# Adafruit_ItsyBitsy_M4.net
KiCad netlist of a schematic drawn in EAGLE
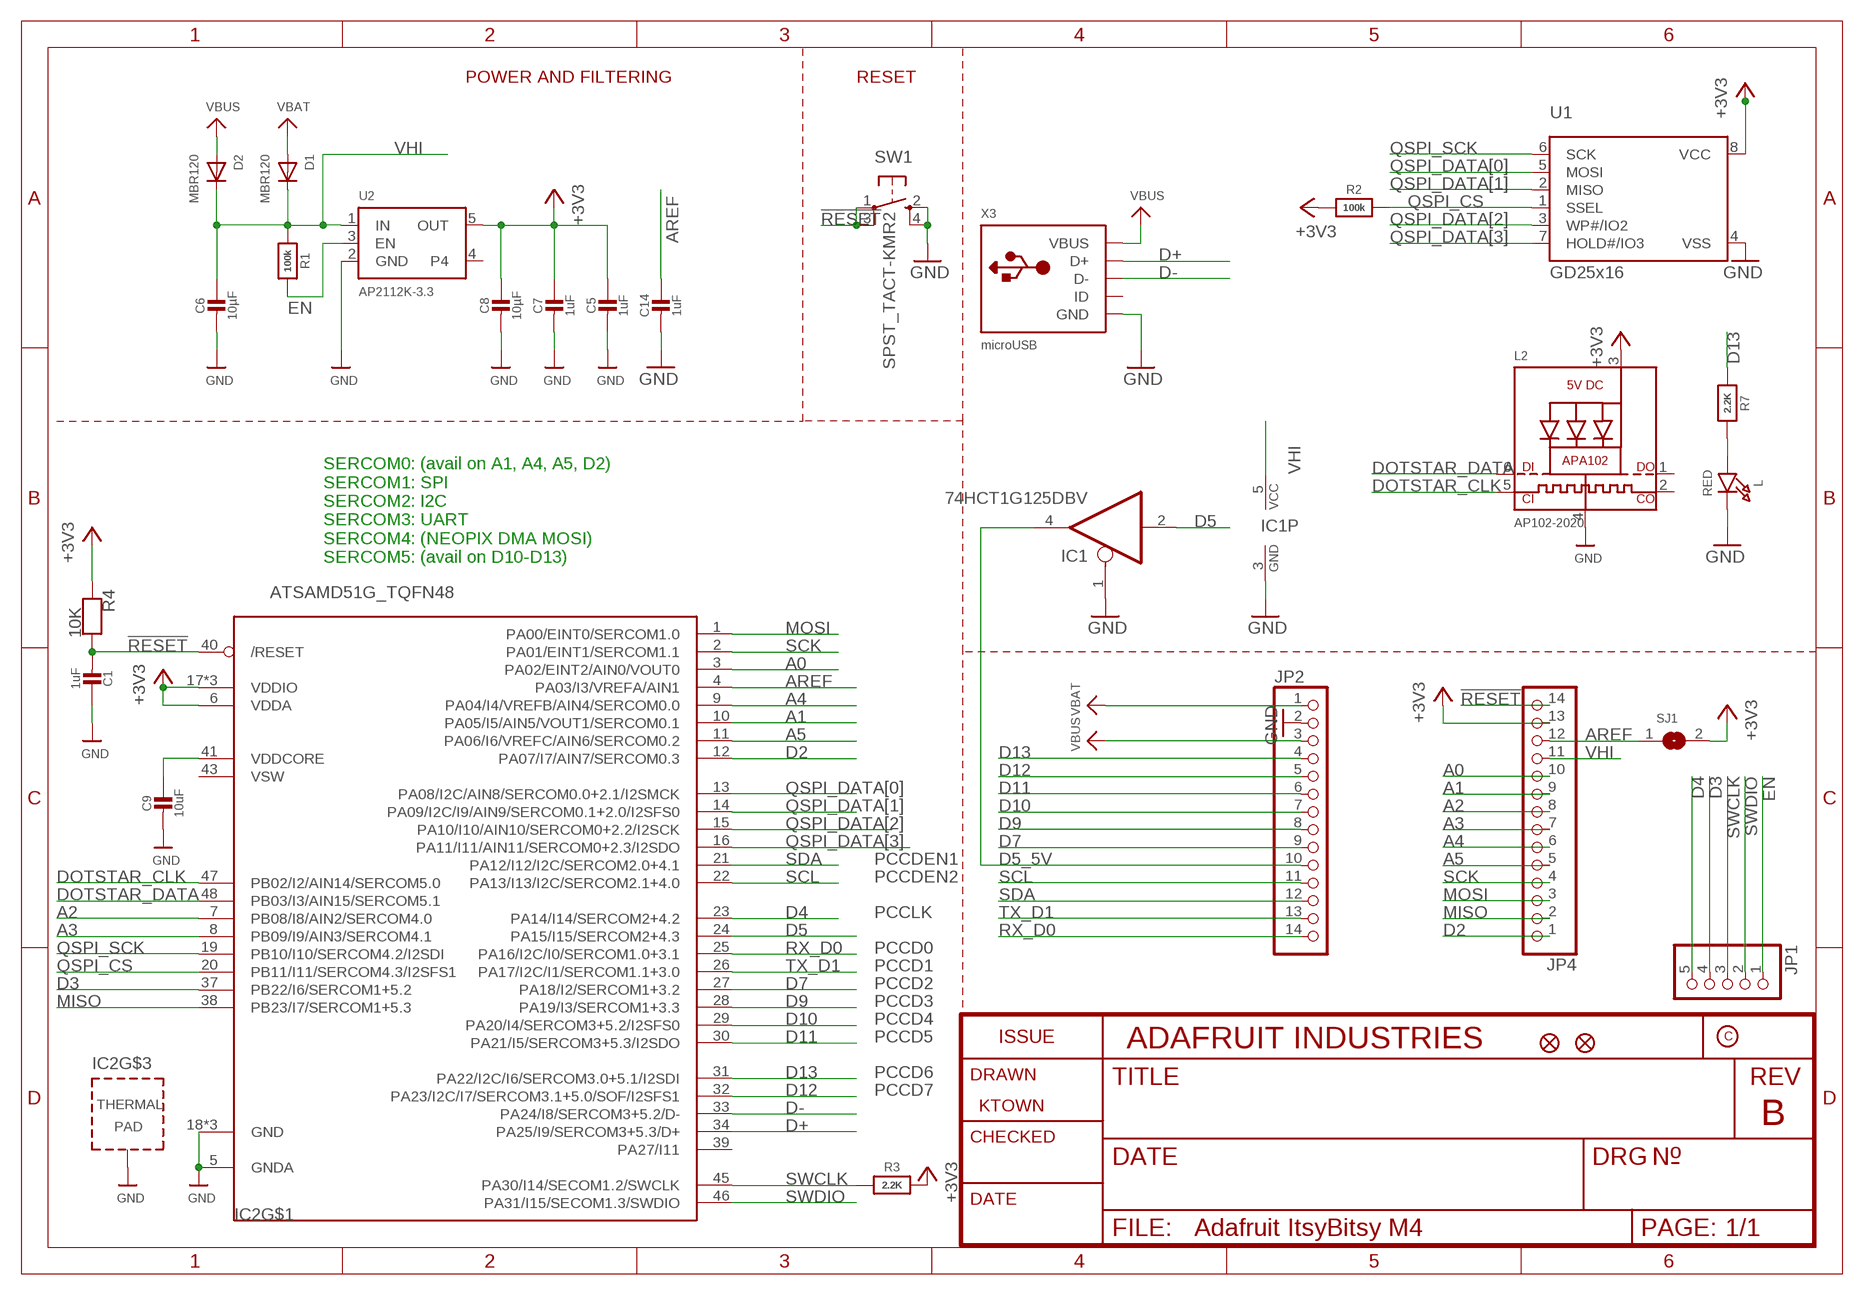
[diagram p0: schematic, sheet 1]

(export (version "E")
  (design (tool "Eeschema 10.0.6"))
  (components
    (comp (ref "C1")
      (value "1uF")
      (footprint "eagle-import:_0603MP")
      (libsource (lib "eagle-import") (part "CAP_CERAMIC_0603MP"))
    )
    (comp (ref "C5")
      (value "1uF")
      (footprint "eagle-import:0603-NO")
      (libsource (lib "eagle-import") (part "CAP_CERAMIC0603_NO"))
    )
    (comp (ref "C6")
      (value "10µF")
      (footprint "eagle-import:0805-NO")
      (libsource (lib "eagle-import") (part "CAP_CERAMIC0805-NOOUTLINE"))
    )
    (comp (ref "C7")
      (value "1uF")
      (footprint "eagle-import:0603-NO")
      (libsource (lib "eagle-import") (part "CAP_CERAMIC0603_NO"))
    )
    (comp (ref "C8")
      (value "10µF")
      (footprint "eagle-import:0805-NO")
      (libsource (lib "eagle-import") (part "CAP_CERAMIC0805-NOOUTLINE"))
    )
    (comp (ref "C9")
      (value "10uF")
      (footprint "eagle-import:_0805MP")
      (libsource (lib "eagle-import") (part "CAP_CERAMIC_0805MP"))
    )
    (comp (ref "C14")
      (value "1uF")
      (footprint "eagle-import:0603-NO")
      (libsource (lib "eagle-import") (part "CAP_CERAMIC0603_NO"))
    )
    (comp (ref "D1")
      (value "MBR120")
      (footprint "eagle-import:SOD-123FL")
      (libsource (lib "eagle-import") (part "DIODE_SOD-123FL"))
    )
    (comp (ref "D2")
      (value "MBR120")
      (footprint "eagle-import:SOD-123FL")
      (libsource (lib "eagle-import") (part "DIODE_SOD-123FL"))
    )
    (comp (ref "IC1")
      (value "74HCT1G125DBV")
      (footprint "eagle-import:SOT23-5")
      (libsource (lib "eagle-import") (part "741G125DBVAHC"))
    )
    (comp (ref "IC2")
      (value "ATSAMD51G_TQFN48")
      (footprint "eagle-import:TQFN48_7MM")
      (libsource (lib "eagle-import") (part "ATSAMD51G_TQFN48"))
    )
    (comp (ref "JP1")
      (value "HEADER-1X570MIL")
      (footprint "eagle-import:1X05_ROUND_70")
      (libsource (lib "eagle-import") (part "HEADER-1X570MIL"))
    )
    (comp (ref "JP2")
      (value "HEADER-1X14")
      (footprint "eagle-import:1X14_ROUND70")
      (libsource (lib "eagle-import") (part "HEADER-1X14"))
    )
    (comp (ref "JP4")
      (value "HEADER-1X14")
      (footprint "eagle-import:1X14_ROUND70")
      (libsource (lib "eagle-import") (part "HEADER-1X14"))
    )
    (comp (ref "L")
      (value "RED")
      (footprint "eagle-import:CHIPLED_0603_NOOUTLINE")
      (libsource (lib "eagle-import") (part "LED0603_NOOUTLINE"))
    )
    (comp (ref "L2")
      (value "AP102-2020")
      (footprint "eagle-import:APA102_2020")
      (libsource (lib "eagle-import") (part "APA1022020"))
    )
    (comp (ref "R1")
      (value "100k")
      (footprint "eagle-import:0603-NO")
      (libsource (lib "eagle-import") (part "RESISTOR_0603_NOOUT"))
    )
    (comp (ref "R2")
      (value "100k")
      (footprint "eagle-import:0603-NO")
      (libsource (lib "eagle-import") (part "RESISTOR_0603_NOOUT"))
    )
    (comp (ref "R3")
      (value "2.2K")
      (footprint "eagle-import:_0603MP")
      (libsource (lib "eagle-import") (part "RESISTOR_0603MP"))
    )
    (comp (ref "R4")
      (value "10K")
      (footprint "eagle-import:_0603MP")
      (libsource (lib "eagle-import") (part "RESISTOR_0603MP"))
    )
    (comp (ref "R7")
      (value "2.2K")
      (footprint "eagle-import:0603-NO")
      (libsource (lib "eagle-import") (part "RESISTOR_0603_NOOUT"))
    )
    (comp (ref "SJ1")
      (value "SOLDERJUMPERCLOSED")
      (footprint "eagle-import:SOLDERJUMPER_CLOSEDWIRE")
      (libsource (lib "eagle-import") (part "SOLDERJUMPERCLOSED"))
    )
    (comp (ref "SW1")
      (value "SPST_TACT-KMR2")
      (footprint "eagle-import:KMR2")
      (libsource (lib "eagle-import") (part "SPST_TACT-KMR2"))
    )
    (comp (ref "U$34")
      (value "FIDUCIAL_1MM")
      (footprint "eagle-import:FIDUCIAL_1MM")
      (libsource (lib "eagle-import") (part "FIDUCIAL_1MM"))
    )
    (comp (ref "U$35")
      (value "FIDUCIAL_1MM")
      (footprint "eagle-import:FIDUCIAL_1MM")
      (libsource (lib "eagle-import") (part "FIDUCIAL_1MM"))
    )
    (comp (ref "U1")
      (value "GD25x16")
      (footprint "eagle-import:USON8")
      (libsource (lib "eagle-import") (part "SPIFLASH_8PINUX"))
    )
    (comp (ref "U2")
      (value "AP2112K-3.3")
      (footprint "eagle-import:SOT23-5")
      (libsource (lib "eagle-import") (part "VREG_SOT23-5"))
    )
    (comp (ref "X3")
      (value "microUSB")
      (footprint "eagle-import:4UCONN_20329_V2")
      (libsource (lib "eagle-import") (part "USB_MICRO_20329_V2"))
    )
  )
  (nets
    (net (code "1") (name "+3V3") (class "Default")
      (node (ref "C5") (pin "1") (pinfunction "1_1") (pintype "passive"))
      (node (ref "C7") (pin "1") (pinfunction "1_1") (pintype "passive"))
      (node (ref "C8") (pin "1") (pinfunction "1_1") (pintype "passive"))
      (node (ref "IC2") (pin "17") (pinfunction "VDDIO_17") (pintype "power_in"))
      (node (ref "IC2") (pin "36") (pinfunction "VDDIO_36") (pintype "power_in"))
      (node (ref "IC2") (pin "44") (pinfunction "VDDIO_44") (pintype "power_in"))
      (node (ref "IC2") (pin "6") (pinfunction "VDDA_6") (pintype "power_in"))
      (node (ref "JP4") (pin "13") (pinfunction "13_13") (pintype "passive"))
      (node (ref "L2") (pin "3") (pinfunction "VDD_3") (pintype "power_in"))
      (node (ref "R2") (pin "1") (pinfunction "1_1") (pintype "passive"))
      (node (ref "R3") (pin "2") (pinfunction "2_2") (pintype "passive"))
      (node (ref "R4") (pin "1") (pinfunction "1_1") (pintype "passive"))
      (node (ref "SJ1") (pin "2") (pinfunction "2_2") (pintype "passive"))
      (node (ref "U1") (pin "8") (pinfunction "VCC_8") (pintype "bidirectional"))
      (node (ref "U2") (pin "5") (pinfunction "OUT_5") (pintype "power_in"))
    )
    (net (code "2") (name "/A0") (class "Default")
      (node (ref "IC2") (pin "3") (pinfunction "PA02/EINT2/AIN0/VOUT0_3") (pintype "bidirectional"))
      (node (ref "JP4") (pin "10") (pinfunction "10_10") (pintype "passive"))
    )
    (net (code "3") (name "/A1") (class "Default")
      (node (ref "IC2") (pin "10") (pinfunction "PA05/I5/AIN5/VOUT1/SERCOM0.1_10") (pintype "bidirectional"))
      (node (ref "JP4") (pin "9") (pinfunction "9_9") (pintype "passive"))
    )
    (net (code "4") (name "/A2") (class "Default")
      (node (ref "IC2") (pin "7") (pinfunction "PB08/I8/AIN2/SERCOM4.0_7") (pintype "bidirectional"))
      (node (ref "JP4") (pin "8") (pinfunction "8_8") (pintype "passive"))
    )
    (net (code "5") (name "/A3") (class "Default")
      (node (ref "IC2") (pin "8") (pinfunction "PB09/I9/AIN3/SERCOM4.1_8") (pintype "bidirectional"))
      (node (ref "JP4") (pin "7") (pinfunction "7_7") (pintype "passive"))
    )
    (net (code "6") (name "/A4") (class "Default")
      (node (ref "IC2") (pin "9") (pinfunction "PA04/I4/VREFB/AIN4/SERCOM0.0_9") (pintype "bidirectional"))
      (node (ref "JP4") (pin "6") (pinfunction "6_6") (pintype "passive"))
    )
    (net (code "7") (name "/A5") (class "Default")
      (node (ref "IC2") (pin "11") (pinfunction "PA06/I6/VREFC/AIN6/SERCOM0.2_11") (pintype "bidirectional"))
      (node (ref "JP4") (pin "5") (pinfunction "5_5") (pintype "passive"))
    )
    (net (code "8") (name "/AREF") (class "Default")
      (node (ref "C14") (pin "1") (pinfunction "1_1") (pintype "passive"))
      (node (ref "IC2") (pin "4") (pinfunction "PA03/I3/VREFA/AIN1_4") (pintype "bidirectional"))
      (node (ref "JP4") (pin "12") (pinfunction "12_12") (pintype "passive"))
      (node (ref "SJ1") (pin "1") (pinfunction "1_1") (pintype "passive"))
    )
    (net (code "9") (name "/D+") (class "Default")
      (node (ref "IC2") (pin "34") (pinfunction "PA25/I9/SERCOM3+5.3/D+_34") (pintype "bidirectional"))
      (node (ref "X3") (pin "D+") (pinfunction "D+_D+") (pintype "bidirectional"))
    )
    (net (code "10") (name "/D-") (class "Default")
      (node (ref "IC2") (pin "33") (pinfunction "PA24/I8/SERCOM3+5.2/D-_33") (pintype "bidirectional"))
      (node (ref "X3") (pin "D-") (pinfunction "D-_D-") (pintype "bidirectional"))
    )
    (net (code "11") (name "/D2") (class "Default")
      (node (ref "IC2") (pin "12") (pinfunction "PA07/I7/AIN7/SERCOM0.3_12") (pintype "bidirectional"))
      (node (ref "JP4") (pin "1") (pinfunction "1_1") (pintype "passive"))
    )
    (net (code "12") (name "/D3") (class "Default")
      (node (ref "IC2") (pin "37") (pinfunction "PB22/I6/SERCOM1+5.2_37") (pintype "bidirectional"))
      (node (ref "JP1") (pin "4") (pinfunction "4_4") (pintype "passive"))
    )
    (net (code "13") (name "/D4") (class "Default")
      (node (ref "IC2") (pin "23") (pinfunction "PA14/I14/SERCOM2+4.2_23") (pintype "bidirectional"))
      (node (ref "JP1") (pin "5") (pinfunction "5_5") (pintype "passive"))
    )
    (net (code "14") (name "/D5") (class "Default")
      (node (ref "IC1") (pin "2") (pinfunction "I_2") (pintype "input"))
      (node (ref "IC2") (pin "24") (pinfunction "PA15/I15/SERCOM2+4.3_24") (pintype "bidirectional"))
    )
    (net (code "15") (name "/D5_5V") (class "Default")
      (node (ref "IC1") (pin "4") (pinfunction "O_4") (pintype "tri_state"))
      (node (ref "JP2") (pin "10") (pinfunction "10_10") (pintype "passive"))
    )
    (net (code "16") (name "/D7") (class "Default")
      (node (ref "IC2") (pin "27") (pinfunction "PA18/I2/SERCOM1+3.2_27") (pintype "bidirectional"))
      (node (ref "JP2") (pin "9") (pinfunction "9_9") (pintype "passive"))
    )
    (net (code "17") (name "/D9") (class "Default")
      (node (ref "IC2") (pin "28") (pinfunction "PA19/I3/SERCOM1+3.3_28") (pintype "bidirectional"))
      (node (ref "JP2") (pin "8") (pinfunction "8_8") (pintype "passive"))
    )
    (net (code "18") (name "/D10") (class "Default")
      (node (ref "IC2") (pin "29") (pinfunction "PA20/I4/SERCOM3+5.2/I2SFS0_29") (pintype "bidirectional"))
      (node (ref "JP2") (pin "7") (pinfunction "7_7") (pintype "passive"))
    )
    (net (code "19") (name "/D11") (class "Default")
      (node (ref "IC2") (pin "30") (pinfunction "PA21/I5/SERCOM3+5.3/I2SDO_30") (pintype "bidirectional"))
      (node (ref "JP2") (pin "6") (pinfunction "6_6") (pintype "passive"))
    )
    (net (code "20") (name "/D12") (class "Default")
      (node (ref "IC2") (pin "32") (pinfunction "PA23/I2C/I7/SERCOM3.1+5.0/SOF/I2SFS1_32") (pintype "bidirectional"))
      (node (ref "JP2") (pin "5") (pinfunction "5_5") (pintype "passive"))
    )
    (net (code "21") (name "/D13") (class "Default")
      (node (ref "IC2") (pin "31") (pinfunction "PA22/I2C/I6/SERCOM3.0+5.1/I2SDI_31") (pintype "bidirectional"))
      (node (ref "JP2") (pin "4") (pinfunction "4_4") (pintype "passive"))
      (node (ref "R7") (pin "1") (pinfunction "1_1") (pintype "passive"))
    )
    (net (code "22") (name "/DOTSTAR_CLK") (class "Default")
      (node (ref "IC2") (pin "47") (pinfunction "PB02/I2/AIN14/SERCOM5.0_47") (pintype "bidirectional"))
      (node (ref "L2") (pin "5") (pinfunction "CKI_5") (pintype "input"))
    )
    (net (code "23") (name "/DOTSTAR_DATA") (class "Default")
      (node (ref "IC2") (pin "48") (pinfunction "PB03/I3/AIN15/SERCOM5.1_48") (pintype "bidirectional"))
      (node (ref "L2") (pin "6") (pinfunction "DI_6") (pintype "input"))
    )
    (net (code "24") (name "/EN") (class "Default")
      (node (ref "JP1") (pin "1") (pinfunction "1_1") (pintype "passive"))
      (node (ref "R1") (pin "2") (pinfunction "2_2") (pintype "passive"))
      (node (ref "U2") (pin "3") (pinfunction "EN_3") (pintype "input"))
    )
    (net (code "25") (name "/MISO") (class "Default")
      (node (ref "IC2") (pin "38") (pinfunction "PB23/I7/SERCOM1+5.3_38") (pintype "bidirectional"))
      (node (ref "JP4") (pin "2") (pinfunction "2_2") (pintype "passive"))
    )
    (net (code "26") (name "/MOSI") (class "Default")
      (node (ref "IC2") (pin "1") (pinfunction "PA00/EINT0/SERCOM1.0_1") (pintype "bidirectional"))
      (node (ref "JP4") (pin "3") (pinfunction "3_3") (pintype "passive"))
    )
    (net (code "27") (name "/QSPI_CS") (class "Default")
      (node (ref "IC2") (pin "20") (pinfunction "PB11/I11/SERCOM4.3/I2SFS1_20") (pintype "bidirectional"))
      (node (ref "R2") (pin "2") (pinfunction "2_2") (pintype "passive"))
      (node (ref "U1") (pin "1") (pinfunction "SSEL_1") (pintype "bidirectional"))
    )
    (net (code "28") (name "/QSPI_DATA[0]") (class "Default")
      (node (ref "IC2") (pin "13") (pinfunction "PA08/I2C/AIN8/SERCOM0.0+2.1/I2SMCK_13") (pintype "bidirectional"))
      (node (ref "U1") (pin "5") (pinfunction "MOSI_5") (pintype "bidirectional"))
    )
    (net (code "29") (name "/QSPI_DATA[1]") (class "Default")
      (node (ref "IC2") (pin "14") (pinfunction "PA09/I2C/I9/AIN9/SERCOM0.1+2.0/I2SFS0_14") (pintype "bidirectional"))
      (node (ref "U1") (pin "2") (pinfunction "MISO_2") (pintype "bidirectional"))
    )
    (net (code "30") (name "/QSPI_DATA[2]") (class "Default")
      (node (ref "IC2") (pin "15") (pinfunction "PA10/I10/AIN10/SERCOM0+2.2/I2SCK_15") (pintype "bidirectional"))
      (node (ref "U1") (pin "3") (pinfunction "WP#/IO2_3") (pintype "bidirectional"))
    )
    (net (code "31") (name "/QSPI_DATA[3]") (class "Default")
      (node (ref "IC2") (pin "16") (pinfunction "PA11/I11/AIN11/SERCOM0+2.3/I2SDO_16") (pintype "bidirectional"))
      (node (ref "U1") (pin "7") (pinfunction "HOLD#/IO3_7") (pintype "bidirectional"))
    )
    (net (code "32") (name "/QSPI_SCK") (class "Default")
      (node (ref "IC2") (pin "19") (pinfunction "PB10/I10/SERCOM4.2/I2SDI_19") (pintype "bidirectional"))
      (node (ref "U1") (pin "6") (pinfunction "SCK_6") (pintype "bidirectional"))
    )
    (net (code "33") (name "/RX_D0") (class "Default")
      (node (ref "IC2") (pin "25") (pinfunction "PA16/I2C/I0/SERCOM1.0+3.1_25") (pintype "bidirectional"))
      (node (ref "JP2") (pin "14") (pinfunction "14_14") (pintype "passive"))
    )
    (net (code "34") (name "/SCK") (class "Default")
      (node (ref "IC2") (pin "2") (pinfunction "PA01/EINT1/SERCOM1.1_2") (pintype "bidirectional"))
      (node (ref "JP4") (pin "4") (pinfunction "4_4") (pintype "passive"))
    )
    (net (code "35") (name "/SCL") (class "Default")
      (node (ref "IC2") (pin "22") (pinfunction "PA13/I13/I2C/SERCOM2.1+4.0_22") (pintype "bidirectional"))
      (node (ref "JP2") (pin "11") (pinfunction "11_11") (pintype "passive"))
    )
    (net (code "36") (name "/SDA") (class "Default")
      (node (ref "IC2") (pin "21") (pinfunction "PA12/I12/I2C/SERCOM2.0+4.1_21") (pintype "bidirectional"))
      (node (ref "JP2") (pin "12") (pinfunction "12_12") (pintype "passive"))
    )
    (net (code "37") (name "/SWCLK") (class "Default")
      (node (ref "IC2") (pin "45") (pinfunction "PA30/I14/SECOM1.2/SWCLK_45") (pintype "bidirectional"))
      (node (ref "JP1") (pin "3") (pinfunction "3_3") (pintype "passive"))
      (node (ref "R3") (pin "1") (pinfunction "1_1") (pintype "passive"))
    )
    (net (code "38") (name "/SWDIO") (class "Default")
      (node (ref "IC2") (pin "46") (pinfunction "PA31/I15/SECOM1.3/SWDIO_46") (pintype "bidirectional"))
      (node (ref "JP1") (pin "2") (pinfunction "2_2") (pintype "passive"))
    )
    (net (code "39") (name "/TX_D1") (class "Default")
      (node (ref "IC2") (pin "26") (pinfunction "PA17/I2C/I1/SERCOM1.1+3.0_26") (pintype "bidirectional"))
      (node (ref "JP2") (pin "13") (pinfunction "13_13") (pintype "passive"))
    )
    (net (code "40") (name "/VHI") (class "Default")
      (node (ref "C6") (pin "1") (pinfunction "1_1") (pintype "passive"))
      (node (ref "D1") (pin "C") (pinfunction "C_C") (pintype "passive"))
      (node (ref "D2") (pin "C") (pinfunction "C_C") (pintype "passive"))
      (node (ref "IC1") (pin "5") (pinfunction "VCC_5") (pintype "power_in"))
      (node (ref "JP4") (pin "11") (pinfunction "11_11") (pintype "passive"))
      (node (ref "R1") (pin "1") (pinfunction "1_1") (pintype "passive"))
      (node (ref "U2") (pin "1") (pinfunction "IN_1") (pintype "power_in"))
    )
    (net (code "41") (name "/VSW") (class "Default")
      (node (ref "IC2") (pin "43") (pinfunction "VSW_43") (pintype "power_in"))
    )
    (net (code "42") (name "/~{RESET}") (class "Default")
      (node (ref "C1") (pin "2") (pinfunction "2_2") (pintype "passive"))
      (node (ref "IC2") (pin "40") (pinfunction "/RESET_40") (pintype "bidirectional"))
      (node (ref "JP4") (pin "14") (pinfunction "14_14") (pintype "passive"))
      (node (ref "R4") (pin "2") (pinfunction "2_2") (pintype "passive"))
      (node (ref "SW1") (pin "1") (pinfunction "P_1") (pintype "passive"))
      (node (ref "SW1") (pin "3") (pinfunction "P1_3") (pintype "passive"))
    )
    (net (code "43") (name "GND") (class "Default")
      (node (ref "C1") (pin "1") (pinfunction "1_1") (pintype "passive"))
      (node (ref "C14") (pin "2") (pinfunction "2_2") (pintype "passive"))
      (node (ref "C5") (pin "2") (pinfunction "2_2") (pintype "passive"))
      (node (ref "C6") (pin "2") (pinfunction "2_2") (pintype "passive"))
      (node (ref "C7") (pin "2") (pinfunction "2_2") (pintype "passive"))
      (node (ref "C8") (pin "2") (pinfunction "2_2") (pintype "passive"))
      (node (ref "C9") (pin "2") (pinfunction "2_2") (pintype "passive"))
      (node (ref "IC1") (pin "1") (pinfunction "OE_1") (pintype "input"))
      (node (ref "IC1") (pin "3") (pinfunction "GND_3") (pintype "power_in"))
      (node (ref "IC2") (pin "18") (pinfunction "GND_18") (pintype "power_in"))
      (node (ref "IC2") (pin "35") (pinfunction "GND_35") (pintype "power_in"))
      (node (ref "IC2") (pin "42") (pinfunction "GND_42") (pintype "power_in"))
      (node (ref "IC2") (pin "5") (pinfunction "GNDA_5") (pintype "power_in"))
      (node (ref "IC2") (pin "THERMAL") (pinfunction "TP_THERMAL") (pintype "power_in"))
      (node (ref "JP2") (pin "2") (pinfunction "2_2") (pintype "passive"))
      (node (ref "L") (pin "C") (pinfunction "C_C") (pintype "passive"))
      (node (ref "L2") (pin "4") (pinfunction "GND_4") (pintype "power_in"))
      (node (ref "SW1") (pin "2") (pinfunction "S_2") (pintype "passive"))
      (node (ref "SW1") (pin "4") (pinfunction "S1_4") (pintype "passive"))
      (node (ref "U1") (pin "4") (pinfunction "VSS_4") (pintype "bidirectional"))
      (node (ref "U2") (pin "2") (pinfunction "GND_2") (pintype "power_in"))
      (node (ref "X3") (pin "BASE@1") (pinfunction "GND_BASE@1") (pintype "power_in"))
      (node (ref "X3") (pin "BASE@2") (pinfunction "GND_BASE@2") (pintype "power_in"))
      (node (ref "X3") (pin "GND") (pinfunction "GND_GND") (pintype "power_in"))
      (node (ref "X3") (pin "SPRT@1") (pinfunction "GND_SPRT@1") (pintype "power_in"))
      (node (ref "X3") (pin "SPRT@2") (pinfunction "GND_SPRT@2") (pintype "power_in"))
      (node (ref "X3") (pin "SPRT@3") (pinfunction "GND_SPRT@3") (pintype "power_in"))
      (node (ref "X3") (pin "SPRT@4") (pinfunction "GND_SPRT@4") (pintype "power_in"))
    )
    (net (code "44") (name "Net-(IC2A-VDDCORE)") (class "Default")
      (node (ref "C9") (pin "1") (pinfunction "1_1") (pintype "passive"))
      (node (ref "IC2") (pin "41") (pinfunction "VDDCORE_41") (pintype "power_in"))
    )
    (net (code "45") (name "Net-(L-PadA)") (class "Default")
      (node (ref "L") (pin "A") (pinfunction "A_A") (pintype "passive"))
      (node (ref "R7") (pin "2") (pinfunction "2_2") (pintype "passive"))
    )
    (net (code "46") (name "VBAT") (class "Default")
      (node (ref "D1") (pin "A") (pinfunction "A_A") (pintype "passive"))
      (node (ref "JP2") (pin "1") (pinfunction "1_1") (pintype "passive"))
    )
    (net (code "47") (name "VBUS") (class "Default")
      (node (ref "D2") (pin "A") (pinfunction "A_A") (pintype "passive"))
      (node (ref "JP2") (pin "3") (pinfunction "3_3") (pintype "passive"))
      (node (ref "X3") (pin "VBUS") (pinfunction "VBUS_VBUS") (pintype "power_in"))
    )
    (net (code "48") (name "unconnected-(IC2A-PA27{slash}I11-Pad39)") (class "Default")
      (node (ref "IC2") (pin "39") (pinfunction "PA27/I11_39") (pintype "bidirectional"))
    )
    (net (code "49") (name "unconnected-(L2-CKO-Pad2)") (class "Default")
      (node (ref "L2") (pin "2") (pinfunction "CKO_2") (pintype "output"))
    )
    (net (code "50") (name "unconnected-(L2-DO-Pad1)") (class "Default")
      (node (ref "L2") (pin "1") (pinfunction "DO_1") (pintype "output"))
    )
    (net (code "51") (name "unconnected-(U2-P4-Pad4)") (class "Default")
      (node (ref "U2") (pin "4") (pinfunction "P4_4") (pintype "bidirectional"))
    )
    (net (code "52") (name "unconnected-(X3-PadID)") (class "Default")
      (node (ref "X3") (pin "ID") (pinfunction "ID_ID") (pintype "bidirectional"))
    )
  )
)
